# H-API_DIST.net
KiCad netlist of a schematic drawn in EAGLE
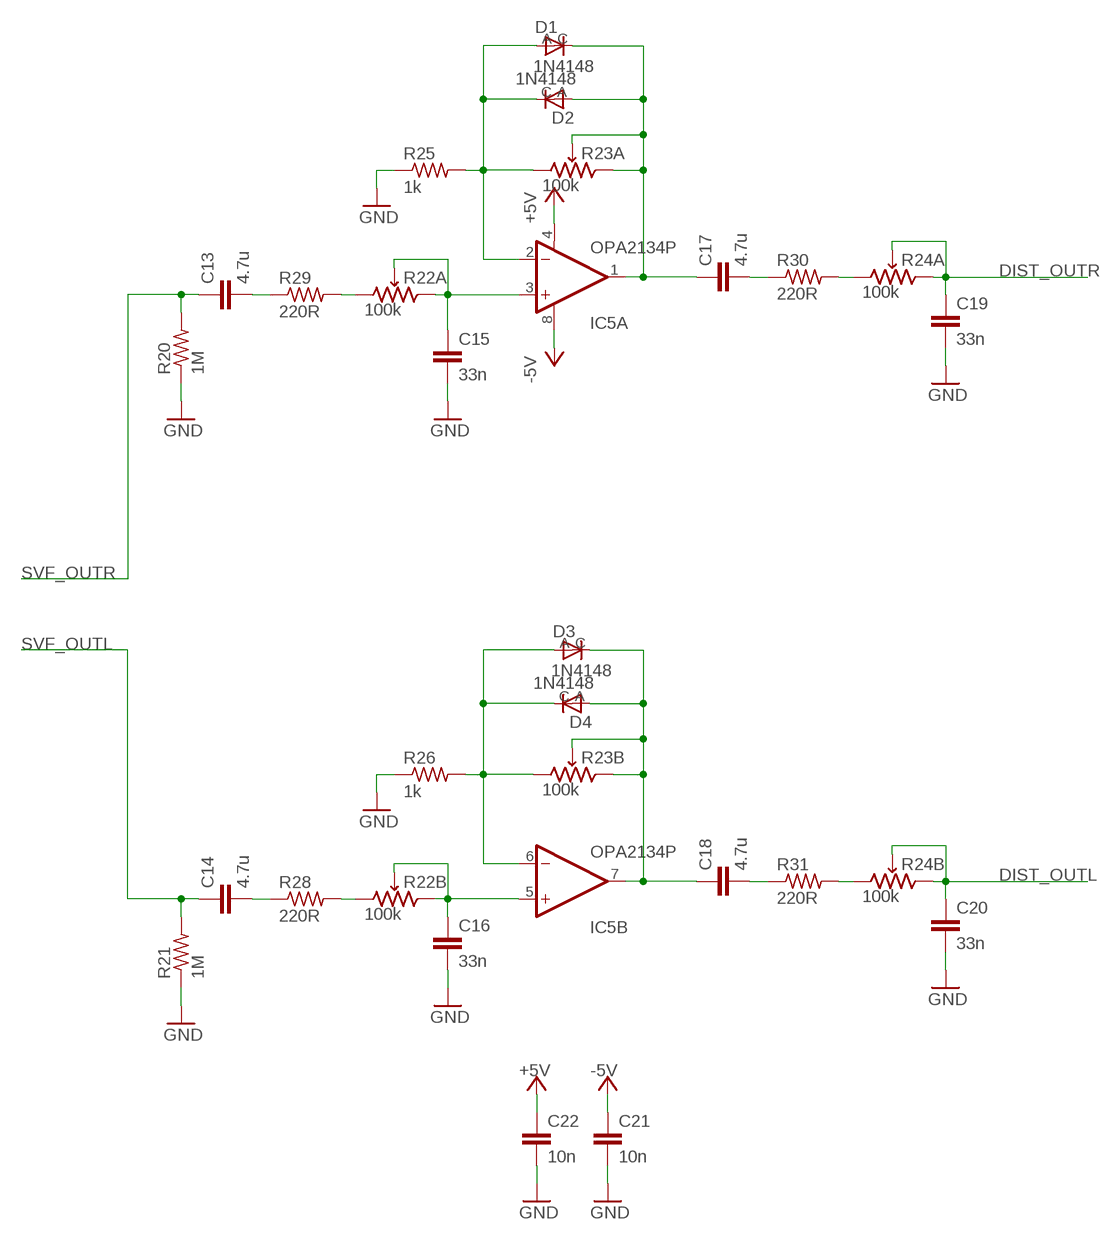
[diagram p0: schematic, sheet 1]

(export (version "E")
  (design (tool "Eeschema 10.0.6"))
  (components
    (comp (ref "C13")
      (value "4.7u")
      (footprint "eagle-import:C0805")
      (libsource (lib "eagle-import") (part "C-EUC0805"))
    )
    (comp (ref "C14")
      (value "4.7u")
      (footprint "eagle-import:C0805")
      (libsource (lib "eagle-import") (part "C-EUC0805"))
    )
    (comp (ref "C15")
      (value "33n")
      (footprint "eagle-import:C0805")
      (libsource (lib "eagle-import") (part "C-EUC0805"))
    )
    (comp (ref "C16")
      (value "33n")
      (footprint "eagle-import:C0805")
      (libsource (lib "eagle-import") (part "C-EUC0805"))
    )
    (comp (ref "C17")
      (value "4.7u")
      (footprint "eagle-import:C0805")
      (libsource (lib "eagle-import") (part "C-EUC0805"))
    )
    (comp (ref "C18")
      (value "4.7u")
      (footprint "eagle-import:C0805")
      (libsource (lib "eagle-import") (part "C-EUC0805"))
    )
    (comp (ref "C19")
      (value "33n")
      (footprint "eagle-import:C0805")
      (libsource (lib "eagle-import") (part "C-EUC0805"))
    )
    (comp (ref "C20")
      (value "33n")
      (footprint "eagle-import:C0805")
      (libsource (lib "eagle-import") (part "C-EUC0805"))
    )
    (comp (ref "C21")
      (value "10n")
      (footprint "eagle-import:C0805")
      (libsource (lib "eagle-import") (part "C-EUC0805"))
    )
    (comp (ref "C22")
      (value "10n")
      (footprint "eagle-import:C0805")
      (libsource (lib "eagle-import") (part "C-EUC0805"))
    )
    (comp (ref "D1")
      (value "1N4148")
      (footprint "eagle-import:DO41-7")
      (libsource (lib "eagle-import") (part "1N4148"))
    )
    (comp (ref "D2")
      (value "1N4148")
      (footprint "eagle-import:DO41-7")
      (libsource (lib "eagle-import") (part "1N4148"))
    )
    (comp (ref "D3")
      (value "1N4148")
      (footprint "eagle-import:DO41-7")
      (libsource (lib "eagle-import") (part "1N4148"))
    )
    (comp (ref "D4")
      (value "1N4148")
      (footprint "eagle-import:DO41-7")
      (libsource (lib "eagle-import") (part "1N4148"))
    )
    (comp (ref "IC5")
      (value "OPA2134P")
      (footprint "eagle-import:DIL08")
      (fields (field (name "MF") "TEXAS INSTRUMENTS") (field (name "MPN") "OPA2134PA"))
      (libsource (lib "eagle-import") (part "OPA2134P"))
    )
    (comp (ref "R20")
      (value "1M")
      (footprint "eagle-import:VMTA55")
      (libsource (lib "eagle-import") (part "R-US_VMTA55"))
    )
    (comp (ref "R21")
      (value "1M")
      (footprint "eagle-import:VMTA55")
      (libsource (lib "eagle-import") (part "R-US_VMTA55"))
    )
    (comp (ref "R22")
      (value "100k")
      (footprint "eagle-import:POT2-SW")
      (libsource (lib "eagle-import") (part "PTR902-2015F-C104"))
    )
    (comp (ref "R23")
      (value "100k")
      (footprint "eagle-import:POT2-SW")
      (libsource (lib "eagle-import") (part "PTR902-2015F-C104"))
    )
    (comp (ref "R24")
      (value "100k")
      (footprint "eagle-import:POT2-SW")
      (libsource (lib "eagle-import") (part "PTR902-2015F-C104"))
    )
    (comp (ref "R25")
      (value "1k")
      (footprint "eagle-import:VMTA55")
      (libsource (lib "eagle-import") (part "R-US_VMTA55"))
    )
    (comp (ref "R26")
      (value "1k")
      (footprint "eagle-import:VMTA55")
      (libsource (lib "eagle-import") (part "R-US_VMTA55"))
    )
    (comp (ref "R28")
      (value "220R")
      (footprint "eagle-import:VMTA55")
      (libsource (lib "eagle-import") (part "R-US_VMTA55"))
    )
    (comp (ref "R29")
      (value "220R")
      (footprint "eagle-import:VMTA55")
      (libsource (lib "eagle-import") (part "R-US_VMTA55"))
    )
    (comp (ref "R30")
      (value "220R")
      (footprint "eagle-import:VMTA55")
      (libsource (lib "eagle-import") (part "R-US_VMTA55"))
    )
    (comp (ref "R31")
      (value "220R")
      (footprint "eagle-import:VMTA55")
      (libsource (lib "eagle-import") (part "R-US_VMTA55"))
    )
  )
  (nets
    (net (code "1") (name "+5V") (class "Default")
      (node (ref "C22") (pin "1") (pinfunction "1_1") (pintype "passive"))
      (node (ref "IC5") (pin "4") (pinfunction "V-_4") (pintype "power_in"))
    )
    (net (code "2") (name "-5V") (class "Default")
      (node (ref "C21") (pin "1") (pinfunction "1_1") (pintype "passive"))
      (node (ref "IC5") (pin "8") (pinfunction "V+_8") (pintype "power_in"))
    )
    (net (code "3") (name "/DIST_OUTL") (class "Default")
      (node (ref "C20") (pin "1") (pinfunction "1_1") (pintype "passive"))
      (node (ref "R24") (pin "2E") (pinfunction "3_2E") (pintype "bidirectional"))
      (node (ref "R24") (pin "2S") (pinfunction "2_2S") (pintype "bidirectional"))
    )
    (net (code "4") (name "/DIST_OUTR") (class "Default")
      (node (ref "C19") (pin "1") (pinfunction "1_1") (pintype "passive"))
      (node (ref "R24") (pin "1E") (pinfunction "3_1E") (pintype "bidirectional"))
      (node (ref "R24") (pin "1S") (pinfunction "2_1S") (pintype "bidirectional"))
    )
    (net (code "5") (name "/SVF_OUTL") (class "Default")
      (node (ref "C14") (pin "1") (pinfunction "1_1") (pintype "passive"))
      (node (ref "R21") (pin "2") (pinfunction "2_2") (pintype "passive"))
    )
    (net (code "6") (name "/SVF_OUTR") (class "Default")
      (node (ref "C13") (pin "1") (pinfunction "1_1") (pintype "passive"))
      (node (ref "R20") (pin "2") (pinfunction "2_2") (pintype "passive"))
    )
    (net (code "7") (name "GND") (class "Default")
      (node (ref "C15") (pin "2") (pinfunction "2_2") (pintype "passive"))
      (node (ref "C16") (pin "2") (pinfunction "2_2") (pintype "passive"))
      (node (ref "C19") (pin "2") (pinfunction "2_2") (pintype "passive"))
      (node (ref "C20") (pin "2") (pinfunction "2_2") (pintype "passive"))
      (node (ref "C21") (pin "2") (pinfunction "2_2") (pintype "passive"))
      (node (ref "C22") (pin "2") (pinfunction "2_2") (pintype "passive"))
      (node (ref "R20") (pin "1") (pinfunction "1_1") (pintype "passive"))
      (node (ref "R21") (pin "1") (pinfunction "1_1") (pintype "passive"))
      (node (ref "R25") (pin "1") (pinfunction "1_1") (pintype "passive"))
      (node (ref "R26") (pin "1") (pinfunction "1_1") (pintype "passive"))
    )
    (net (code "8") (name "Net-(C13-Pad2)") (class "Default")
      (node (ref "C13") (pin "2") (pinfunction "2_2") (pintype "passive"))
      (node (ref "R29") (pin "1") (pinfunction "1_1") (pintype "passive"))
    )
    (net (code "9") (name "Net-(C14-Pad2)") (class "Default")
      (node (ref "C14") (pin "2") (pinfunction "2_2") (pintype "passive"))
      (node (ref "R28") (pin "1") (pinfunction "1_1") (pintype "passive"))
    )
    (net (code "10") (name "Net-(C17-Pad2)") (class "Default")
      (node (ref "C17") (pin "2") (pinfunction "2_2") (pintype "passive"))
      (node (ref "R30") (pin "1") (pinfunction "1_1") (pintype "passive"))
    )
    (net (code "11") (name "Net-(C18-Pad2)") (class "Default")
      (node (ref "C18") (pin "2") (pinfunction "2_2") (pintype "passive"))
      (node (ref "R31") (pin "1") (pinfunction "1_1") (pintype "passive"))
    )
    (net (code "12") (name "Net-(D1-P$1)") (class "Default")
      (node (ref "D1") (pin "A") (pinfunction "P$1_A") (pintype "bidirectional"))
      (node (ref "D2") (pin "C") (pinfunction "P$2_C") (pintype "bidirectional"))
      (node (ref "IC5") (pin "2") (pinfunction "-IN_2") (pintype "input"))
      (node (ref "R23") (pin "1A") (pinfunction "1_1A") (pintype "bidirectional"))
      (node (ref "R25") (pin "2") (pinfunction "2_2") (pintype "passive"))
    )
    (net (code "13") (name "Net-(D1-P$2)") (class "Default")
      (node (ref "C17") (pin "1") (pinfunction "1_1") (pintype "passive"))
      (node (ref "D1") (pin "C") (pinfunction "P$2_C") (pintype "bidirectional"))
      (node (ref "D2") (pin "A") (pinfunction "P$1_A") (pintype "bidirectional"))
      (node (ref "IC5") (pin "1") (pinfunction "OUT_1") (pintype "output"))
      (node (ref "R23") (pin "1E") (pinfunction "3_1E") (pintype "bidirectional"))
      (node (ref "R23") (pin "1S") (pinfunction "2_1S") (pintype "bidirectional"))
    )
    (net (code "14") (name "Net-(D3-P$1)") (class "Default")
      (node (ref "D3") (pin "A") (pinfunction "P$1_A") (pintype "bidirectional"))
      (node (ref "D4") (pin "C") (pinfunction "P$2_C") (pintype "bidirectional"))
      (node (ref "IC5") (pin "6") (pinfunction "-IN_6") (pintype "input"))
      (node (ref "R23") (pin "2A") (pinfunction "1_2A") (pintype "bidirectional"))
      (node (ref "R26") (pin "2") (pinfunction "2_2") (pintype "passive"))
    )
    (net (code "15") (name "Net-(D3-P$2)") (class "Default")
      (node (ref "C18") (pin "1") (pinfunction "1_1") (pintype "passive"))
      (node (ref "D3") (pin "C") (pinfunction "P$2_C") (pintype "bidirectional"))
      (node (ref "D4") (pin "A") (pinfunction "P$1_A") (pintype "bidirectional"))
      (node (ref "IC5") (pin "7") (pinfunction "OUT_7") (pintype "output"))
      (node (ref "R23") (pin "2E") (pinfunction "3_2E") (pintype "bidirectional"))
      (node (ref "R23") (pin "2S") (pinfunction "2_2S") (pintype "bidirectional"))
    )
    (net (code "16") (name "Net-(IC5A-+IN)") (class "Default")
      (node (ref "C15") (pin "1") (pinfunction "1_1") (pintype "passive"))
      (node (ref "IC5") (pin "3") (pinfunction "+IN_3") (pintype "input"))
      (node (ref "R22") (pin "1E") (pinfunction "3_1E") (pintype "bidirectional"))
      (node (ref "R22") (pin "1S") (pinfunction "2_1S") (pintype "bidirectional"))
    )
    (net (code "17") (name "Net-(IC5B-+IN)") (class "Default")
      (node (ref "C16") (pin "1") (pinfunction "1_1") (pintype "passive"))
      (node (ref "IC5") (pin "5") (pinfunction "+IN_5") (pintype "input"))
      (node (ref "R22") (pin "2E") (pinfunction "3_2E") (pintype "bidirectional"))
      (node (ref "R22") (pin "2S") (pinfunction "2_2S") (pintype "bidirectional"))
    )
    (net (code "18") (name "Net-(R22B-1)") (class "Default")
      (node (ref "R22") (pin "1A") (pinfunction "1_1A") (pintype "bidirectional"))
      (node (ref "R29") (pin "2") (pinfunction "2_2") (pintype "passive"))
    )
    (net (code "19") (name "Net-(R22C-1)") (class "Default")
      (node (ref "R22") (pin "2A") (pinfunction "1_2A") (pintype "bidirectional"))
      (node (ref "R28") (pin "2") (pinfunction "2_2") (pintype "passive"))
    )
    (net (code "20") (name "Net-(R24B-1)") (class "Default")
      (node (ref "R24") (pin "1A") (pinfunction "1_1A") (pintype "bidirectional"))
      (node (ref "R30") (pin "2") (pinfunction "2_2") (pintype "passive"))
    )
    (net (code "21") (name "Net-(R24C-1)") (class "Default")
      (node (ref "R24") (pin "2A") (pinfunction "1_2A") (pintype "bidirectional"))
      (node (ref "R31") (pin "2") (pinfunction "2_2") (pintype "passive"))
    )
  )
)
